# braids_v50.net
KiCad netlist of a schematic drawn in EAGLE
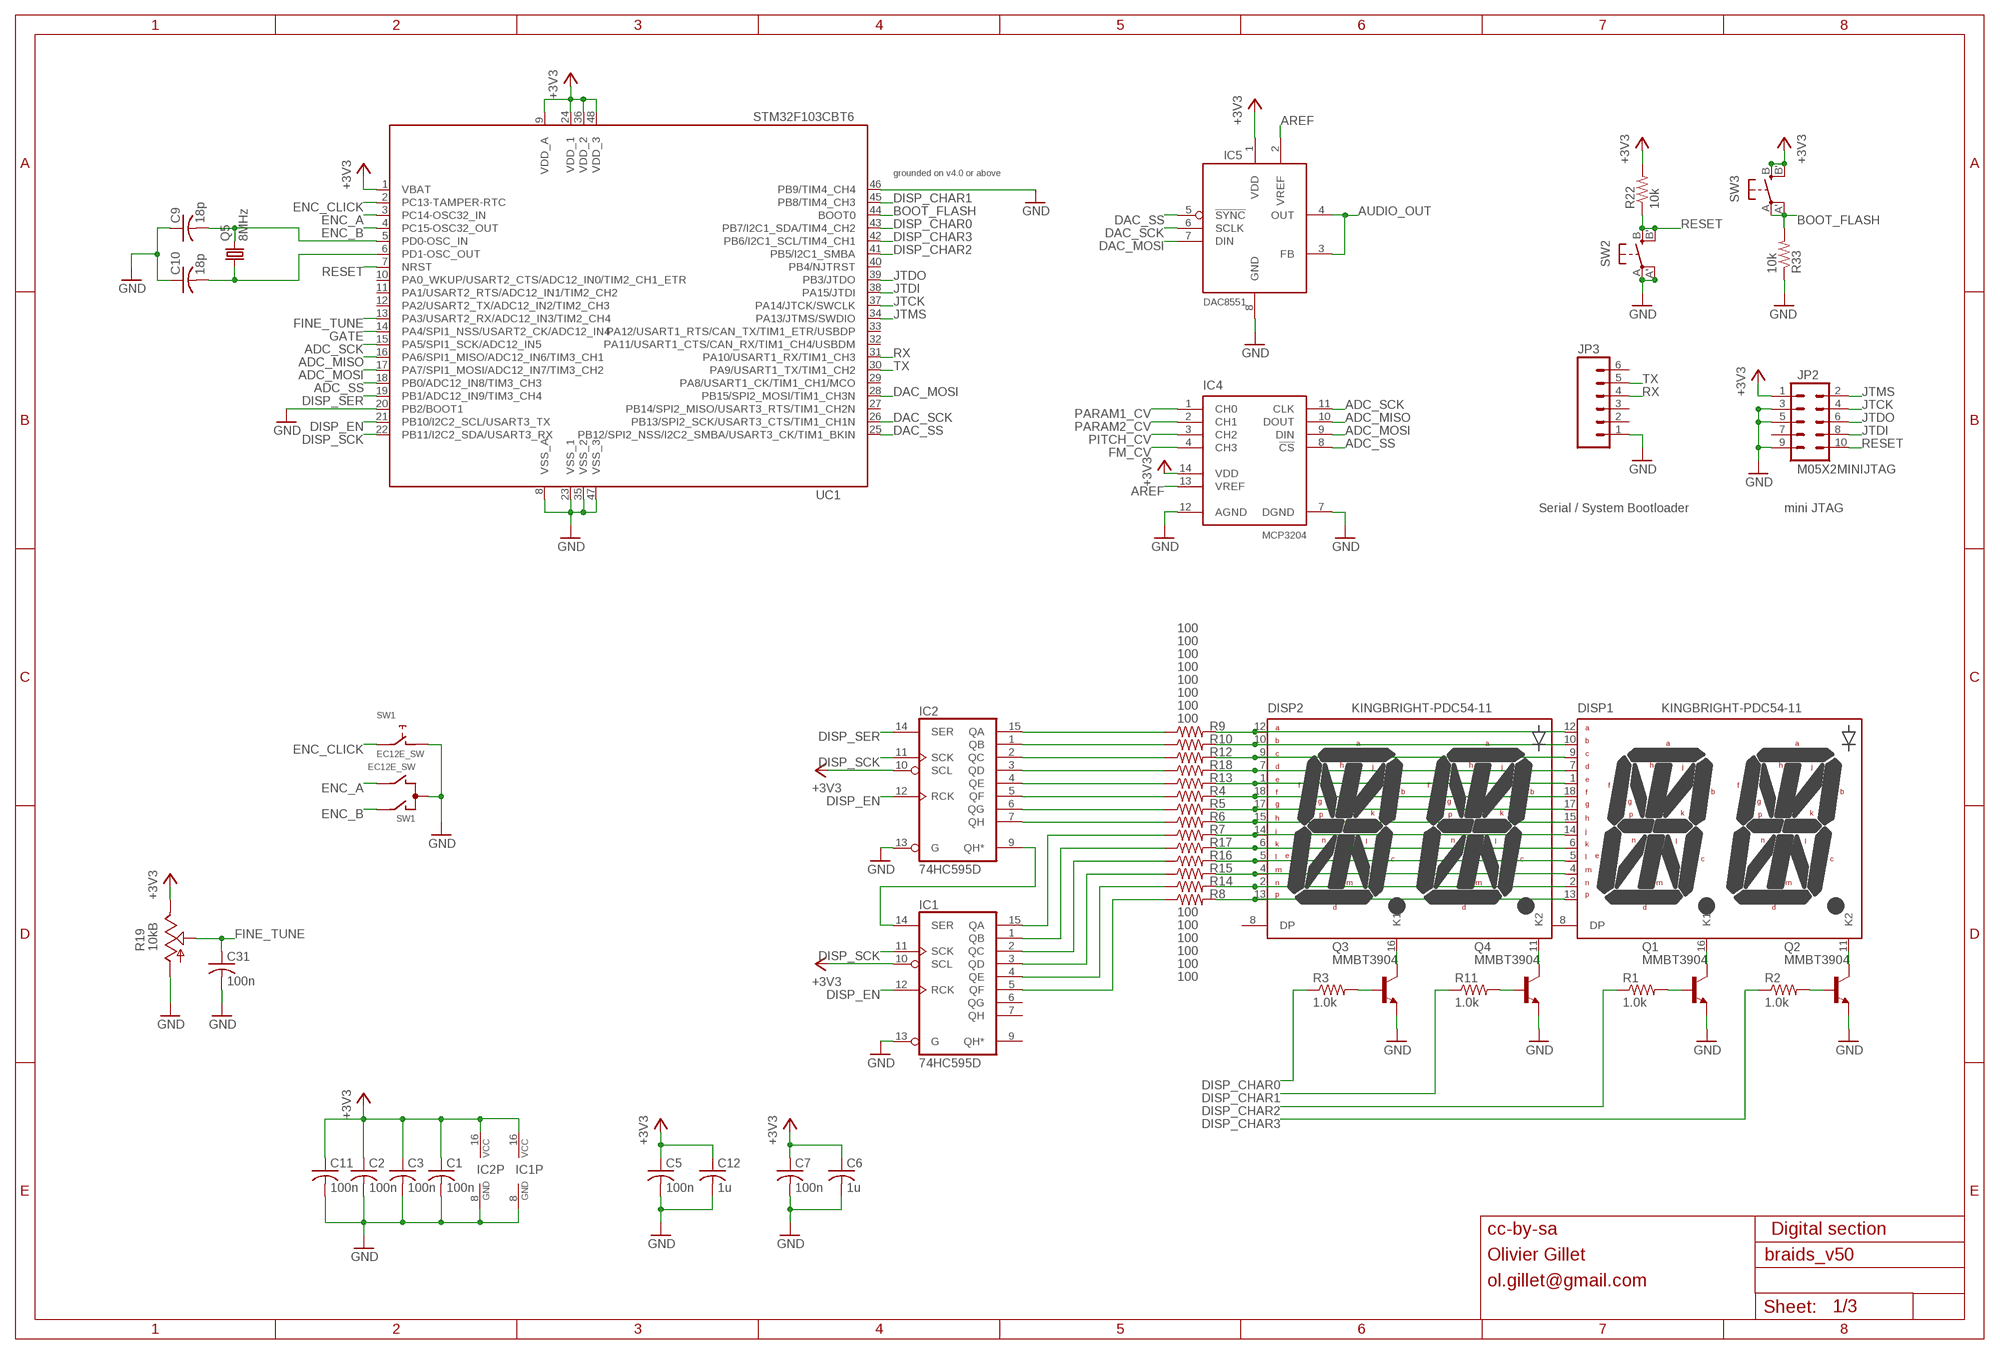
[diagram p0: schematic, sheet 1]
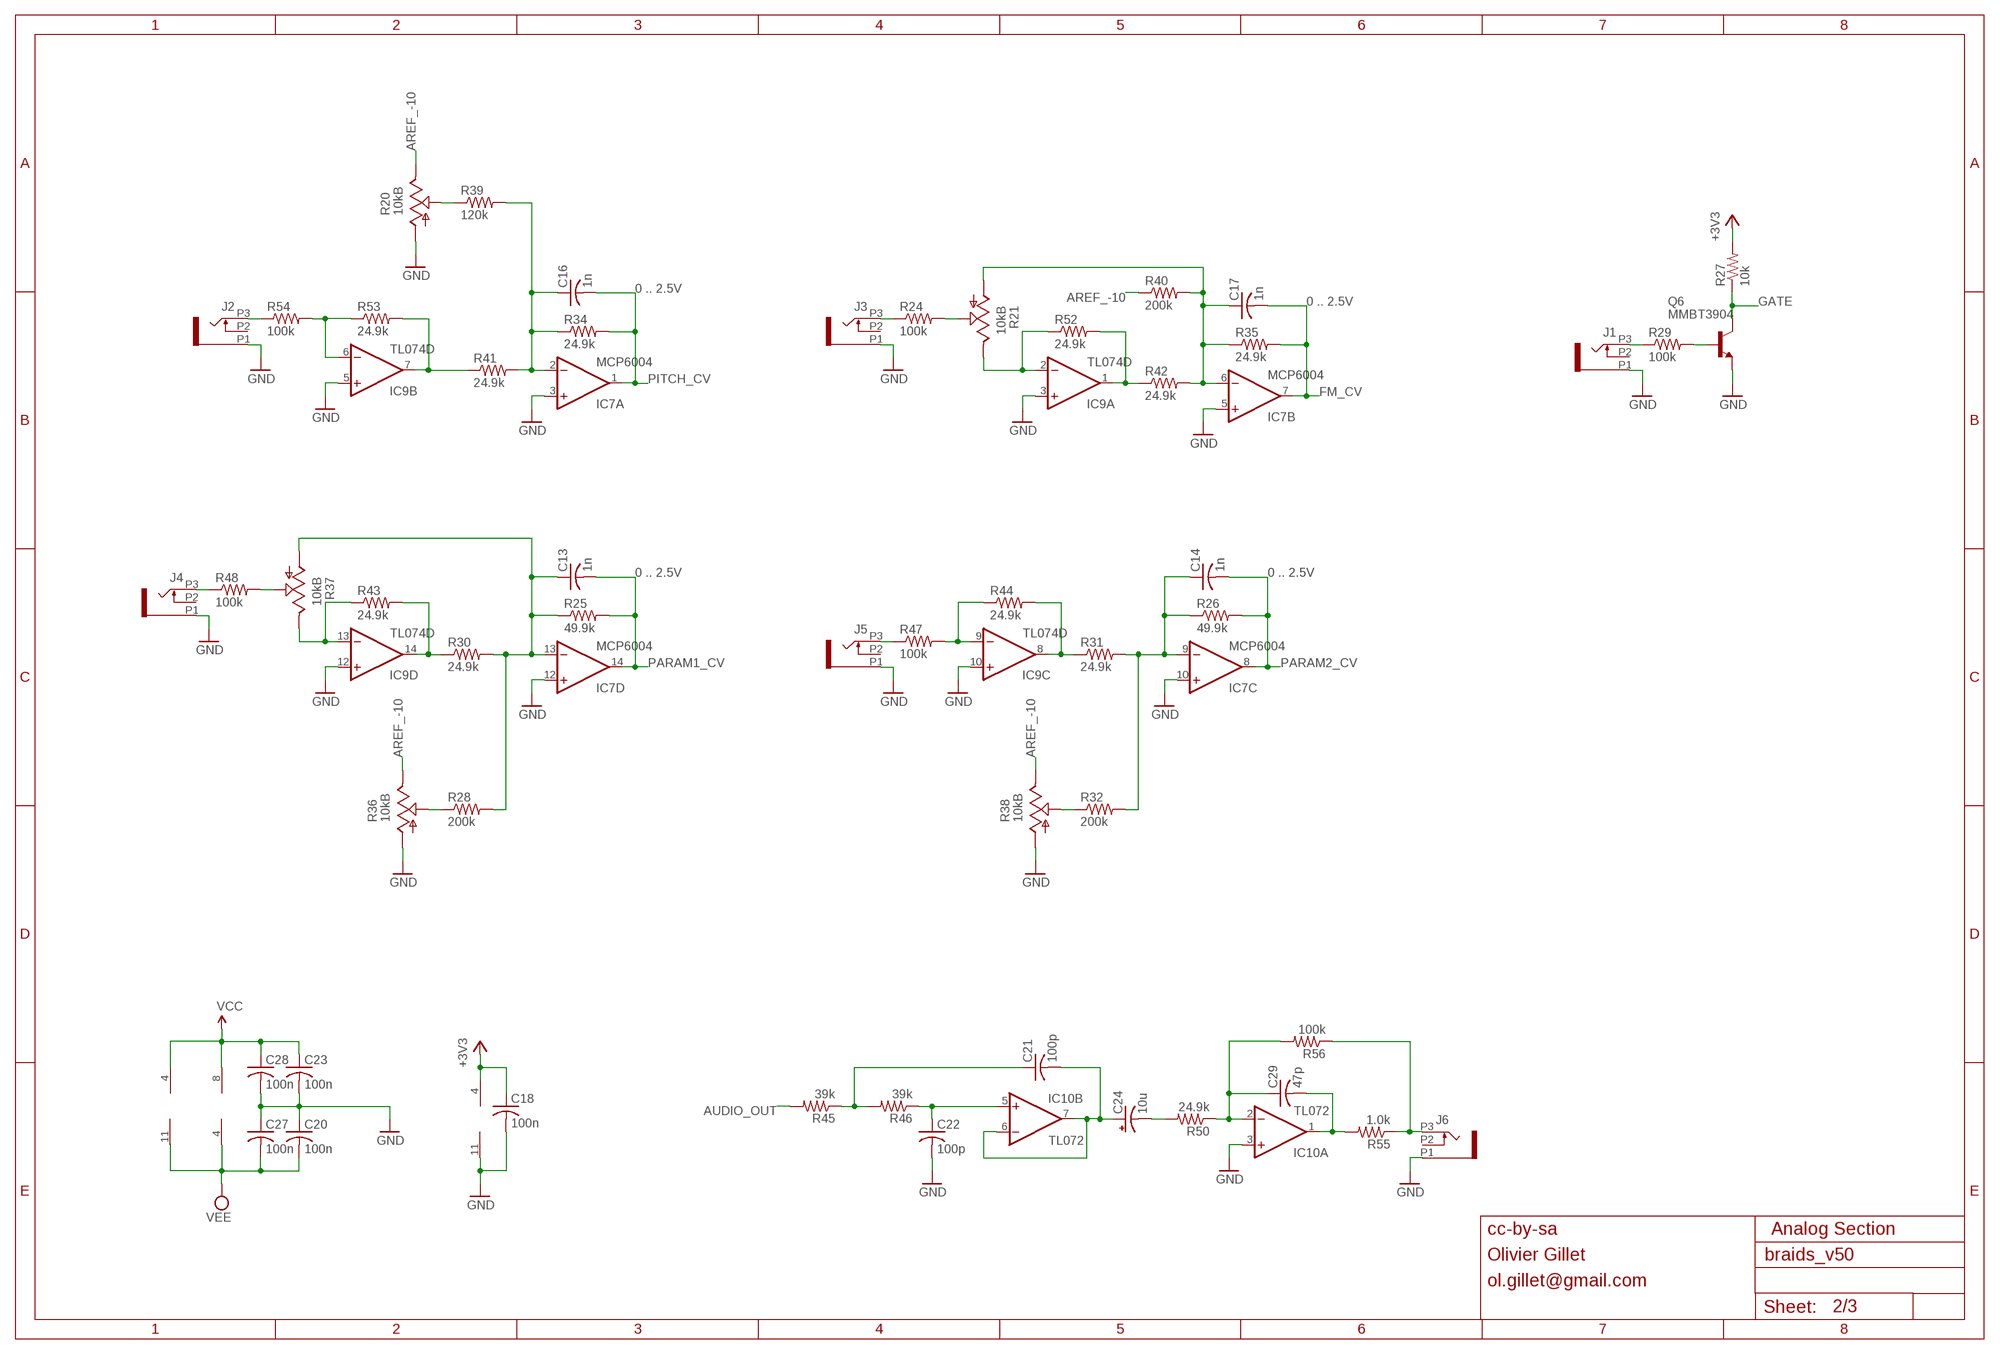
[diagram p1: schematic, sheet 2]
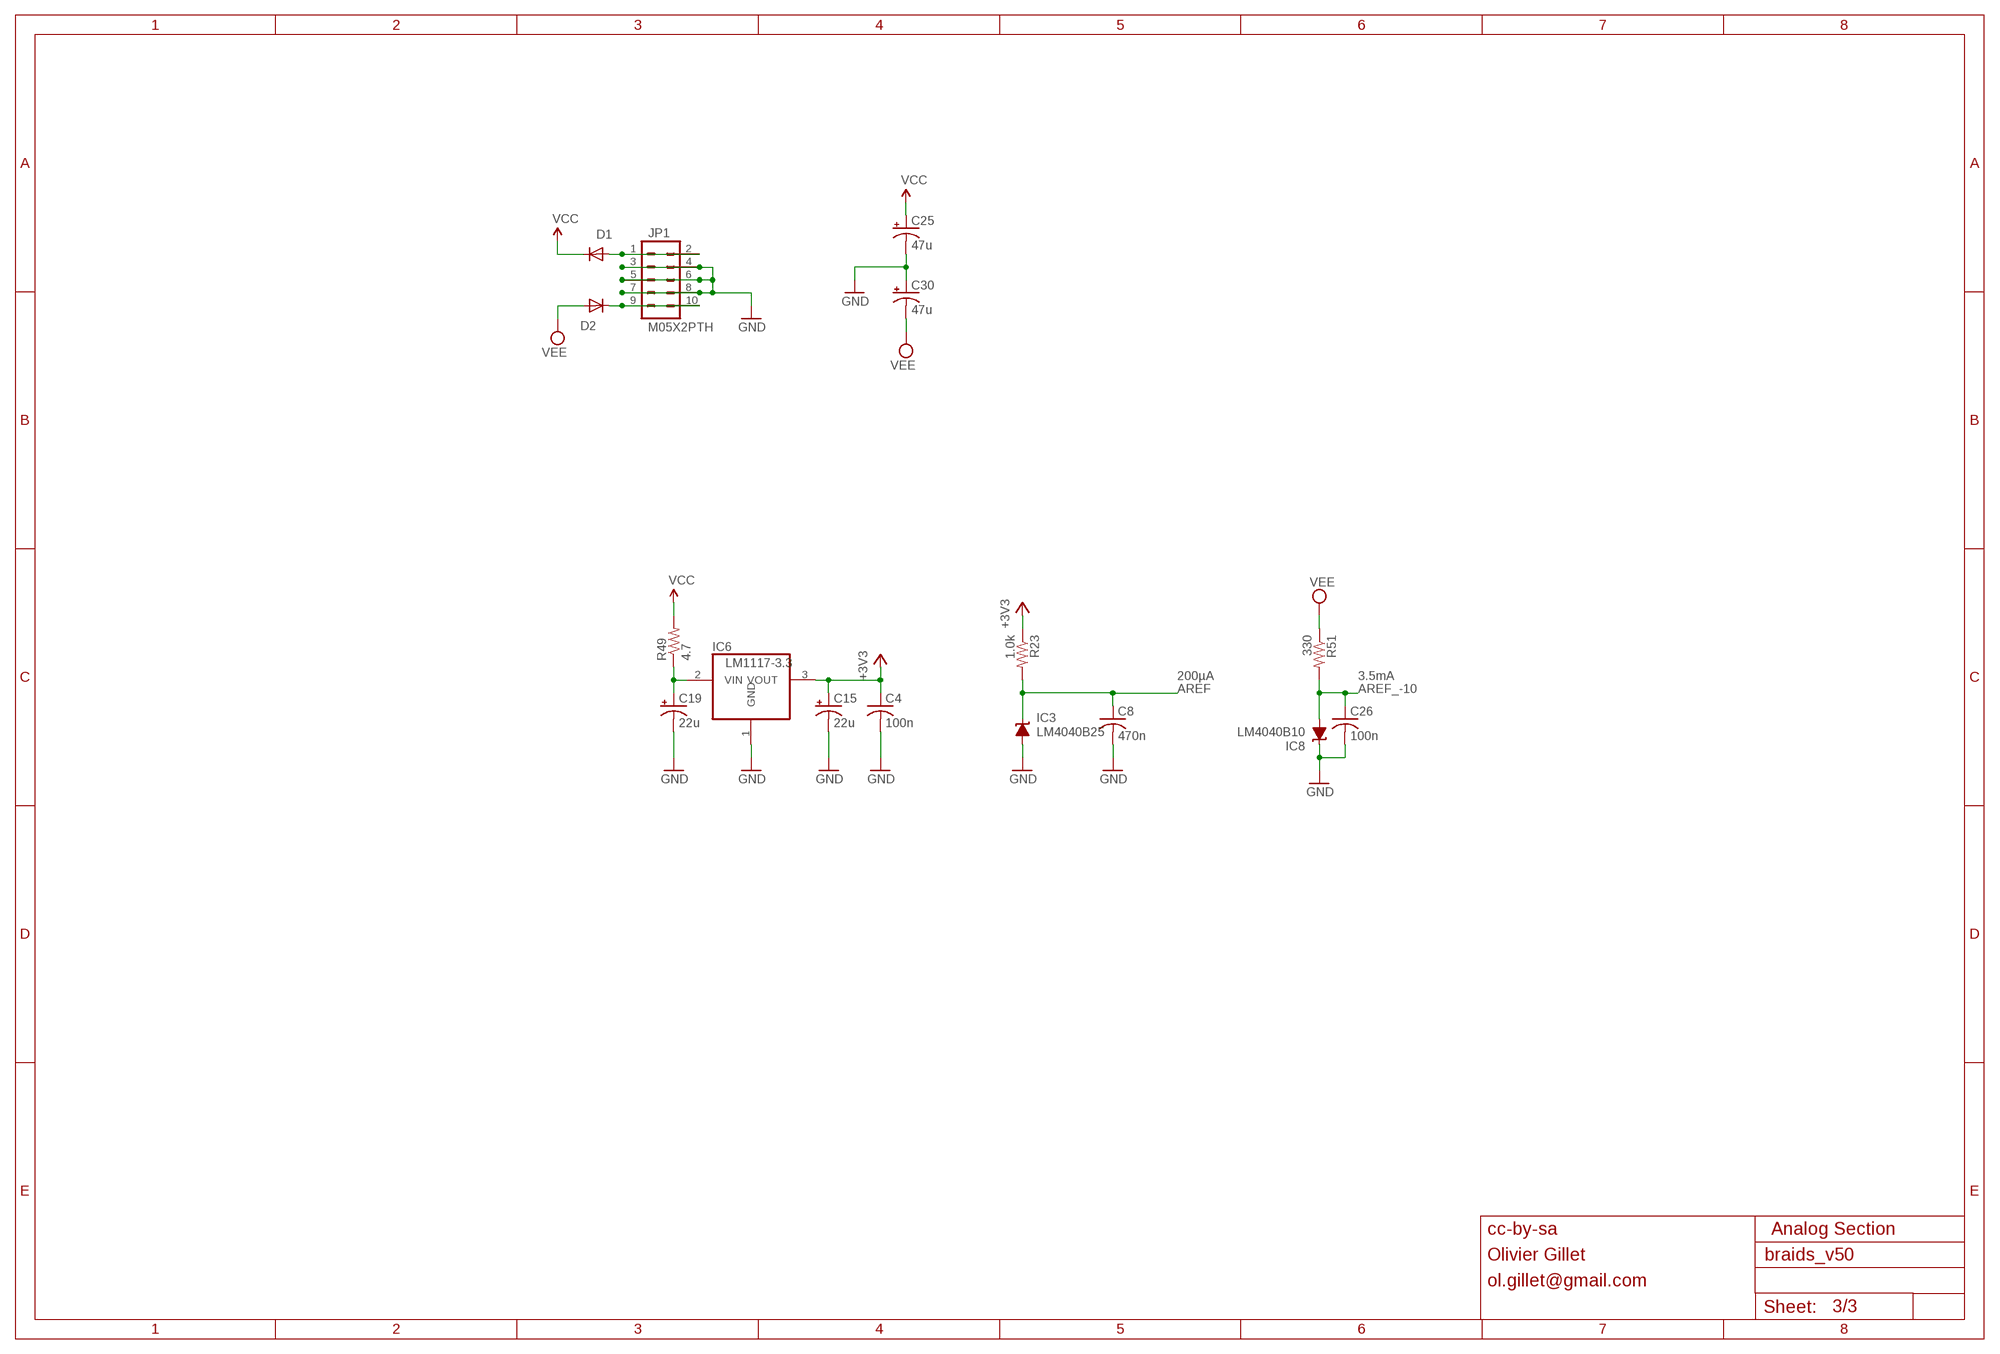
[diagram p2: schematic, sheet 3]

(export (version "E")
  (design (tool "Eeschema 10.0.6"))
  (components
    (comp (ref "C13")
      (value "1n")
      (footprint "eagle-import:C0603")
      (libsource (lib "eagle-import") (part "C-USC0603"))
    )
    (comp (ref "C14")
      (value "1n")
      (footprint "eagle-import:C0603")
      (libsource (lib "eagle-import") (part "C-USC0603"))
    )
    (comp (ref "C16")
      (value "1n")
      (footprint "eagle-import:C0603")
      (libsource (lib "eagle-import") (part "C-USC0603"))
    )
    (comp (ref "C17")
      (value "1n")
      (footprint "eagle-import:C0603")
      (libsource (lib "eagle-import") (part "C-USC0603"))
    )
    (comp (ref "C18")
      (value "100n")
      (footprint "eagle-import:C0603")
      (libsource (lib "eagle-import") (part "C-USC0603"))
    )
    (comp (ref "C20")
      (value "100n")
      (footprint "eagle-import:C0603")
      (libsource (lib "eagle-import") (part "C-USC0603"))
    )
    (comp (ref "C21")
      (value "100p")
      (footprint "eagle-import:C0603")
      (libsource (lib "eagle-import") (part "C-USC0603"))
    )
    (comp (ref "C22")
      (value "100p")
      (footprint "eagle-import:C0603")
      (libsource (lib "eagle-import") (part "C-USC0603"))
    )
    (comp (ref "C23")
      (value "100n")
      (footprint "eagle-import:C0603")
      (libsource (lib "eagle-import") (part "C-USC0603"))
    )
    (comp (ref "C24")
      (value "10u")
      (footprint "eagle-import:PANASONIC_B")
      (libsource (lib "eagle-import") (part "CPOL-USB"))
    )
    (comp (ref "C27")
      (value "100n")
      (footprint "eagle-import:C0603")
      (libsource (lib "eagle-import") (part "C-USC0603"))
    )
    (comp (ref "C28")
      (value "100n")
      (footprint "eagle-import:C0603")
      (libsource (lib "eagle-import") (part "C-USC0603"))
    )
    (comp (ref "C29")
      (value "47p")
      (footprint "eagle-import:C0603")
      (libsource (lib "eagle-import") (part "C-USC0603"))
    )
    (comp (ref "IC7")
      (value "MCP6004")
      (footprint "eagle-import:SO14")
      (libsource (lib "eagle-import") (part "TL074D"))
    )
    (comp (ref "IC9")
      (value "TL074D")
      (footprint "eagle-import:SO14")
      (libsource (lib "eagle-import") (part "TL074D"))
    )
    (comp (ref "IC10")
      (value "TL072")
      (footprint "eagle-import:SO08")
      (libsource (lib "eagle-import") (part "TL072D"))
    )
    (comp (ref "J1")
      (value "PJ301_THONKICONN6")
      (footprint "eagle-import:WQP_PJ_301M6")
      (libsource (lib "eagle-import") (part "PJ301_THONKICONN6"))
    )
    (comp (ref "J2")
      (value "PJ301_THONKICONN6")
      (footprint "eagle-import:WQP_PJ_301M6")
      (libsource (lib "eagle-import") (part "PJ301_THONKICONN6"))
    )
    (comp (ref "J3")
      (value "PJ301_THONKICONN6")
      (footprint "eagle-import:WQP_PJ_301M6")
      (libsource (lib "eagle-import") (part "PJ301_THONKICONN6"))
    )
    (comp (ref "J4")
      (value "PJ301_THONKICONN6")
      (footprint "eagle-import:WQP_PJ_301M6")
      (libsource (lib "eagle-import") (part "PJ301_THONKICONN6"))
    )
    (comp (ref "J5")
      (value "PJ301_THONKICONN6")
      (footprint "eagle-import:WQP_PJ_301M6")
      (libsource (lib "eagle-import") (part "PJ301_THONKICONN6"))
    )
    (comp (ref "J6")
      (value "PJ301_THONKICONN6")
      (footprint "eagle-import:WQP_PJ_301M6")
      (libsource (lib "eagle-import") (part "PJ301_THONKICONN6"))
    )
    (comp (ref "Q6")
      (value "MMBT3904")
      (footprint "eagle-import:SOT23-BEC")
      (libsource (lib "eagle-import") (part "-NPN-SOT23-BECMMBT3904LT1"))
    )
    (comp (ref "R20")
      (value "10kB")
      (footprint "eagle-import:ALPS_POT_VERTICAL_PS")
      (libsource (lib "eagle-import") (part "POT_USVERTICAL_PS"))
    )
    (comp (ref "R21")
      (value "10kB")
      (footprint "eagle-import:ALPS_POT_VERTICAL_PS")
      (libsource (lib "eagle-import") (part "POT_USVERTICAL_PS"))
    )
    (comp (ref "R24")
      (value "100k")
      (footprint "eagle-import:R0603")
      (libsource (lib "eagle-import") (part "R-US_R0603"))
    )
    (comp (ref "R25")
      (value "49.9k")
      (footprint "eagle-import:R0603")
      (libsource (lib "eagle-import") (part "R-US_R0603"))
    )
    (comp (ref "R26")
      (value "49.9k")
      (footprint "eagle-import:R0603")
      (libsource (lib "eagle-import") (part "R-US_R0603"))
    )
    (comp (ref "R27")
      (value "10k")
      (footprint "eagle-import:R0603")
      (libsource (lib "eagle-import") (part "R-US_R0603"))
    )
    (comp (ref "R28")
      (value "200k")
      (footprint "eagle-import:R0603")
      (libsource (lib "eagle-import") (part "R-US_R0603"))
    )
    (comp (ref "R29")
      (value "100k")
      (footprint "eagle-import:R0603")
      (libsource (lib "eagle-import") (part "R-US_R0603"))
    )
    (comp (ref "R30")
      (value "24.9k")
      (footprint "eagle-import:R0603")
      (libsource (lib "eagle-import") (part "R-US_R0603"))
    )
    (comp (ref "R31")
      (value "24.9k")
      (footprint "eagle-import:R0603")
      (libsource (lib "eagle-import") (part "R-US_R0603"))
    )
    (comp (ref "R32")
      (value "200k")
      (footprint "eagle-import:R0603")
      (libsource (lib "eagle-import") (part "R-US_R0603"))
    )
    (comp (ref "R34")
      (value "24.9k")
      (footprint "eagle-import:R0603")
      (libsource (lib "eagle-import") (part "R-US_R0603"))
    )
    (comp (ref "R35")
      (value "24.9k")
      (footprint "eagle-import:R0603")
      (libsource (lib "eagle-import") (part "R-US_R0603"))
    )
    (comp (ref "R36")
      (value "10kB")
      (footprint "eagle-import:ALPS_POT_VERTICAL_PS")
      (libsource (lib "eagle-import") (part "POT_USVERTICAL_PS"))
    )
    (comp (ref "R37")
      (value "10kB")
      (footprint "eagle-import:ALPS_POT_VERTICAL_PS")
      (libsource (lib "eagle-import") (part "POT_USVERTICAL_PS"))
    )
    (comp (ref "R38")
      (value "10kB")
      (footprint "eagle-import:ALPS_POT_VERTICAL_PS")
      (libsource (lib "eagle-import") (part "POT_USVERTICAL_PS"))
    )
    (comp (ref "R39")
      (value "120k")
      (footprint "eagle-import:R0603")
      (libsource (lib "eagle-import") (part "R-US_R0603"))
    )
    (comp (ref "R40")
      (value "200k")
      (footprint "eagle-import:R0603")
      (libsource (lib "eagle-import") (part "R-US_R0603"))
    )
    (comp (ref "R41")
      (value "24.9k")
      (footprint "eagle-import:R0603")
      (libsource (lib "eagle-import") (part "R-US_R0603"))
    )
    (comp (ref "R42")
      (value "24.9k")
      (footprint "eagle-import:R0603")
      (libsource (lib "eagle-import") (part "R-US_R0603"))
    )
    (comp (ref "R43")
      (value "24.9k")
      (footprint "eagle-import:R0603")
      (libsource (lib "eagle-import") (part "R-US_R0603"))
    )
    (comp (ref "R44")
      (value "24.9k")
      (footprint "eagle-import:R0603")
      (libsource (lib "eagle-import") (part "R-US_R0603"))
    )
    (comp (ref "R45")
      (value "39k")
      (footprint "eagle-import:R0603")
      (libsource (lib "eagle-import") (part "R-US_R0603"))
    )
    (comp (ref "R46")
      (value "39k")
      (footprint "eagle-import:R0603")
      (libsource (lib "eagle-import") (part "R-US_R0603"))
    )
    (comp (ref "R47")
      (value "100k")
      (footprint "eagle-import:R0603")
      (libsource (lib "eagle-import") (part "R-US_R0603"))
    )
    (comp (ref "R48")
      (value "100k")
      (footprint "eagle-import:R0603")
      (libsource (lib "eagle-import") (part "R-US_R0603"))
    )
    (comp (ref "R50")
      (value "24.9k")
      (footprint "eagle-import:R0603")
      (libsource (lib "eagle-import") (part "R-US_R0603"))
    )
    (comp (ref "R52")
      (value "24.9k")
      (footprint "eagle-import:R0603")
      (libsource (lib "eagle-import") (part "R-US_R0603"))
    )
    (comp (ref "R53")
      (value "24.9k")
      (footprint "eagle-import:R0603")
      (libsource (lib "eagle-import") (part "R-US_R0603"))
    )
    (comp (ref "R54")
      (value "100k")
      (footprint "eagle-import:R0603")
      (libsource (lib "eagle-import") (part "R-US_R0603"))
    )
    (comp (ref "R55")
      (value "1.0k")
      (footprint "eagle-import:R0603")
      (libsource (lib "eagle-import") (part "R-US_R0603"))
    )
    (comp (ref "R56")
      (value "100k")
      (footprint "eagle-import:R0603")
      (libsource (lib "eagle-import") (part "R-US_R0603"))
    )
    (comp (ref "C1")
      (value "100n")
      (footprint "eagle-import:C0603")
      (libsource (lib "eagle-import") (part "C-USC0603"))
    )
    (comp (ref "C2")
      (value "100n")
      (footprint "eagle-import:C0603")
      (libsource (lib "eagle-import") (part "C-USC0603"))
    )
    (comp (ref "C3")
      (value "100n")
      (footprint "eagle-import:C0603")
      (libsource (lib "eagle-import") (part "C-USC0603"))
    )
    (comp (ref "C5")
      (value "100n")
      (footprint "eagle-import:C0603")
      (libsource (lib "eagle-import") (part "C-USC0603"))
    )
    (comp (ref "C6")
      (value "1u")
      (footprint "eagle-import:C0603")
      (libsource (lib "eagle-import") (part "C-USC0603"))
    )
    (comp (ref "C7")
      (value "100n")
      (footprint "eagle-import:C0603")
      (libsource (lib "eagle-import") (part "C-USC0603"))
    )
    (comp (ref "C9")
      (value "18p")
      (footprint "eagle-import:C0603")
      (libsource (lib "eagle-import") (part "C-USC0603"))
    )
    (comp (ref "C10")
      (value "18p")
      (footprint "eagle-import:C0603")
      (libsource (lib "eagle-import") (part "C-USC0603"))
    )
    (comp (ref "C11")
      (value "100n")
      (footprint "eagle-import:C0603")
      (libsource (lib "eagle-import") (part "C-USC0603"))
    )
    (comp (ref "C12")
      (value "1u")
      (footprint "eagle-import:C0603")
      (libsource (lib "eagle-import") (part "C-USC0603"))
    )
    (comp (ref "C31")
      (value "100n")
      (footprint "eagle-import:C0603")
      (libsource (lib "eagle-import") (part "C-USC0603"))
    )
    (comp (ref "DISP1")
      (value "KINGBRIGHT-PDC54-11")
      (footprint "eagle-import:PDC54")
      (libsource (lib "eagle-import") (part "KINGBRIGHT-PDC54-11"))
    )
    (comp (ref "DISP2")
      (value "KINGBRIGHT-PDC54-11")
      (footprint "eagle-import:PDC54")
      (libsource (lib "eagle-import") (part "KINGBRIGHT-PDC54-11"))
    )
    (comp (ref "IC1")
      (value "74HC595D")
      (footprint "eagle-import:SO16")
      (libsource (lib "eagle-import") (part "74595DHC"))
    )
    (comp (ref "IC2")
      (value "74HC595D")
      (footprint "eagle-import:SO16")
      (libsource (lib "eagle-import") (part "74595DHC"))
    )
    (comp (ref "IC4")
      (value "MCP3204")
      (footprint "eagle-import:SO14")
      (libsource (lib "eagle-import") (part "MCP3302"))
    )
    (comp (ref "IC5")
      (value "DAC8551")
      (footprint "eagle-import:MSOP-8")
      (libsource (lib "eagle-import") (part "DAC855X"))
    )
    (comp (ref "JP2")
      (value "M05X2MINIJTAG")
      (footprint "eagle-import:2X5-1.27")
      (libsource (lib "eagle-import") (part "M05X2MINIJTAG"))
    )
    (comp (ref "JP3")
      (value "M06SIP")
      (footprint "eagle-import:1X06")
      (libsource (lib "eagle-import") (part "M06SIP"))
    )
    (comp (ref "Q1")
      (value "MMBT3904")
      (footprint "eagle-import:SOT23-BEC")
      (libsource (lib "eagle-import") (part "-NPN-SOT23-BECMMBT3904LT1"))
    )
    (comp (ref "Q2")
      (value "MMBT3904")
      (footprint "eagle-import:SOT23-BEC")
      (libsource (lib "eagle-import") (part "-NPN-SOT23-BECMMBT3904LT1"))
    )
    (comp (ref "Q3")
      (value "MMBT3904")
      (footprint "eagle-import:SOT23-BEC")
      (libsource (lib "eagle-import") (part "-NPN-SOT23-BECMMBT3904LT1"))
    )
    (comp (ref "Q4")
      (value "MMBT3904")
      (footprint "eagle-import:SOT23-BEC")
      (libsource (lib "eagle-import") (part "-NPN-SOT23-BECMMBT3904LT1"))
    )
    (comp (ref "Q5")
      (value "8MHz")
      (footprint "eagle-import:HC49UP")
      (libsource (lib "eagle-import") (part "CRYSTALHC49UP"))
    )
    (comp (ref "R1")
      (value "1.0k")
      (footprint "eagle-import:R0603")
      (libsource (lib "eagle-import") (part "R-US_R0603"))
    )
    (comp (ref "R2")
      (value "1.0k")
      (footprint "eagle-import:R0603")
      (libsource (lib "eagle-import") (part "R-US_R0603"))
    )
    (comp (ref "R3")
      (value "1.0k")
      (footprint "eagle-import:R0603")
      (libsource (lib "eagle-import") (part "R-US_R0603"))
    )
    (comp (ref "R4")
      (value "100")
      (footprint "eagle-import:R0603")
      (libsource (lib "eagle-import") (part "R-US_R0603"))
    )
    (comp (ref "R5")
      (value "100")
      (footprint "eagle-import:R0603")
      (libsource (lib "eagle-import") (part "R-US_R0603"))
    )
    (comp (ref "R6")
      (value "100")
      (footprint "eagle-import:R0603")
      (libsource (lib "eagle-import") (part "R-US_R0603"))
    )
    (comp (ref "R7")
      (value "100")
      (footprint "eagle-import:R0603")
      (libsource (lib "eagle-import") (part "R-US_R0603"))
    )
    (comp (ref "R8")
      (value "100")
      (footprint "eagle-import:R0603")
      (libsource (lib "eagle-import") (part "R-US_R0603"))
    )
    (comp (ref "R9")
      (value "100")
      (footprint "eagle-import:R0603")
      (libsource (lib "eagle-import") (part "R-US_R0603"))
    )
    (comp (ref "R10")
      (value "100")
      (footprint "eagle-import:R0603")
      (libsource (lib "eagle-import") (part "R-US_R0603"))
    )
    (comp (ref "R11")
      (value "1.0k")
      (footprint "eagle-import:R0603")
      (libsource (lib "eagle-import") (part "R-US_R0603"))
    )
    (comp (ref "R12")
      (value "100")
      (footprint "eagle-import:R0603")
      (libsource (lib "eagle-import") (part "R-US_R0603"))
    )
    (comp (ref "R13")
      (value "100")
      (footprint "eagle-import:R0603")
      (libsource (lib "eagle-import") (part "R-US_R0603"))
    )
    (comp (ref "R14")
      (value "100")
      (footprint "eagle-import:R0603")
      (libsource (lib "eagle-import") (part "R-US_R0603"))
    )
    (comp (ref "R15")
      (value "100")
      (footprint "eagle-import:R0603")
      (libsource (lib "eagle-import") (part "R-US_R0603"))
    )
    (comp (ref "R16")
      (value "100")
      (footprint "eagle-import:R0603")
      (libsource (lib "eagle-import") (part "R-US_R0603"))
    )
    (comp (ref "R17")
      (value "100")
      (footprint "eagle-import:R0603")
      (libsource (lib "eagle-import") (part "R-US_R0603"))
    )
    (comp (ref "R18")
      (value "100")
      (footprint "eagle-import:R0603")
      (libsource (lib "eagle-import") (part "R-US_R0603"))
    )
    (comp (ref "R19")
      (value "10kB")
      (footprint "eagle-import:ALPS_POT_VERTICAL_PS")
      (libsource (lib "eagle-import") (part "POT_USVERTICAL_PS"))
    )
    (comp (ref "R22")
      (value "10k")
      (footprint "eagle-import:R0603")
      (libsource (lib "eagle-import") (part "R-US_R0603"))
    )
    (comp (ref "R33")
      (value "10k")
      (footprint "eagle-import:R0603")
      (libsource (lib "eagle-import") (part "R-US_R0603"))
    )
    (comp (ref "SW1")
      (value "EC12E_SW")
      (footprint "eagle-import:ALPS_EC12E_SW")
      (libsource (lib "eagle-import") (part "EC12E_SW"))
    )
    (comp (ref "SW2")
      (value "EVQQ2")
      (footprint "eagle-import:EVQ-Q2")
      (libsource (lib "eagle-import") (part "EVQQ2"))
    )
    (comp (ref "SW3")
      (value "EVQQ2")
      (footprint "eagle-import:EVQ-Q2")
      (libsource (lib "eagle-import") (part "EVQQ2"))
    )
    (comp (ref "UC1")
      (value "STM32F103CBT6")
      (footprint "eagle-import:LQFP48")
      (libsource (lib "eagle-import") (part "STM32F103CB"))
    )
    (comp (ref "C4")
      (value "100n")
      (footprint "eagle-import:C0603")
      (libsource (lib "eagle-import") (part "C-USC0603"))
    )
    (comp (ref "C8")
      (value "470n")
      (footprint "eagle-import:C0603")
      (libsource (lib "eagle-import") (part "C-USC0603"))
    )
    (comp (ref "C15")
      (value "22u")
      (footprint "eagle-import:PANASONIC_C")
      (libsource (lib "eagle-import") (part "CPOL-USC"))
    )
    (comp (ref "C19")
      (value "22u")
      (footprint "eagle-import:PANASONIC_C")
      (libsource (lib "eagle-import") (part "CPOL-USC"))
    )
    (comp (ref "C25")
      (value "47u")
      (footprint "eagle-import:PANASONIC_D")
      (libsource (lib "eagle-import") (part "CPOL-USD"))
    )
    (comp (ref "C26")
      (value "100n")
      (footprint "eagle-import:C0603")
      (libsource (lib "eagle-import") (part "C-USC0603"))
    )
    (comp (ref "C30")
      (value "47u")
      (footprint "eagle-import:PANASONIC_D")
      (libsource (lib "eagle-import") (part "CPOL-USD"))
    )
    (comp (ref "D1")
      (value "1N5819HW")
      (footprint "eagle-import:SOD123")
      (libsource (lib "eagle-import") (part "DIODE-SOD123"))
    )
    (comp (ref "D2")
      (value "1N5819HW")
      (footprint "eagle-import:SOD123")
      (libsource (lib "eagle-import") (part "DIODE-SOD123"))
    )
    (comp (ref "IC3")
      (value "LM4040B25")
      (footprint "eagle-import:DBZ_R-PDSO-G3")
      (libsource (lib "eagle-import") (part "LM4041DBZB12"))
    )
    (comp (ref "IC6")
      (value "LM1117-3.3")
      (footprint "eagle-import:TO252")
      (libsource (lib "eagle-import") (part "REG1117T"))
    )
    (comp (ref "IC8")
      (value "LM4040B10")
      (footprint "eagle-import:DBZ_R-PDSO-G3")
      (libsource (lib "eagle-import") (part "LM4041DBZB12"))
    )
    (comp (ref "JP1")
      (value "M05X2PTH")
      (footprint "eagle-import:AVR_ICSP")
      (libsource (lib "eagle-import") (part "M05X2PTH"))
    )
    (comp (ref "R23")
      (value "1.0k")
      (footprint "eagle-import:R0603")
      (libsource (lib "eagle-import") (part "R-US_R0603"))
    )
    (comp (ref "R49")
      (value "4.7")
      (footprint "eagle-import:R1206")
      (libsource (lib "eagle-import") (part "R-US_R1206"))
    )
    (comp (ref "R51")
      (value "330")
      (footprint "eagle-import:R0603")
      (libsource (lib "eagle-import") (part "R-US_R0603"))
    )
  )
  (nets
    (net (code "1") (name "+3V3") (class "Default")
      (node (ref "C1") (pin "1") (pinfunction "1_1") (pintype "passive"))
      (node (ref "C11") (pin "1") (pinfunction "1_1") (pintype "passive"))
      (node (ref "C12") (pin "1") (pinfunction "1_1") (pintype "passive"))
      (node (ref "C15") (pin "+") (pinfunction "+_+") (pintype "passive"))
      (node (ref "C18") (pin "1") (pinfunction "1_1") (pintype "passive"))
      (node (ref "C2") (pin "1") (pinfunction "1_1") (pintype "passive"))
      (node (ref "C3") (pin "1") (pinfunction "1_1") (pintype "passive"))
      (node (ref "C4") (pin "1") (pinfunction "1_1") (pintype "passive"))
      (node (ref "C5") (pin "1") (pinfunction "1_1") (pintype "passive"))
      (node (ref "C6") (pin "1") (pinfunction "1_1") (pintype "passive"))
      (node (ref "C7") (pin "1") (pinfunction "1_1") (pintype "passive"))
      (node (ref "IC1") (pin "10") (pinfunction "SCL_10") (pintype "input"))
      (node (ref "IC1") (pin "16") (pinfunction "VCC_16") (pintype "power_in"))
      (node (ref "IC2") (pin "10") (pinfunction "SCL_10") (pintype "input"))
      (node (ref "IC2") (pin "16") (pinfunction "VCC_16") (pintype "power_in"))
      (node (ref "IC4") (pin "14") (pinfunction "VDD_14") (pintype "bidirectional"))
      (node (ref "IC5") (pin "1") (pinfunction "VDD_1") (pintype "power_in"))
      (node (ref "IC6") (pin "3") (pinfunction "VOUT_3") (pintype "output"))
      (node (ref "IC7") (pin "4") (pinfunction "V+_4") (pintype "power_in"))
      (node (ref "JP2") (pin "1") (pinfunction "1_1") (pintype "passive"))
      (node (ref "R19") (pin "P$1") (pinfunction "E_P$1") (pintype "passive"))
      (node (ref "R22") (pin "2") (pinfunction "2_2") (pintype "passive"))
      (node (ref "R23") (pin "1") (pinfunction "1_1") (pintype "passive"))
      (node (ref "R27") (pin "2") (pinfunction "2_2") (pintype "passive"))
      (node (ref "SW3") (pin "B") (pinfunction "S_B") (pintype "passive"))
      (node (ref "SW3") (pin "B'") (pinfunction "S1_B'") (pintype "passive"))
      (node (ref "UC1") (pin "1") (pinfunction "VBAT_1") (pintype "power_in"))
      (node (ref "UC1") (pin "24") (pinfunction "VDD_1_24") (pintype "power_in"))
      (node (ref "UC1") (pin "36") (pinfunction "VDD_2_36") (pintype "power_in"))
      (node (ref "UC1") (pin "48") (pinfunction "VDD_3_48") (pintype "power_in"))
      (node (ref "UC1") (pin "9") (pinfunction "VDD_A_9") (pintype "power_in"))
    )
    (net (code "2") (name "ADC_MISO") (class "Default")
      (node (ref "IC4") (pin "10") (pinfunction "DOUT_10") (pintype "bidirectional"))
      (node (ref "UC1") (pin "16") (pinfunction "PA6/SPI1_MISO/ADC12_IN6/TIM3_CH1_16") (pintype "bidirectional"))
    )
    (net (code "3") (name "ADC_MOSI") (class "Default")
      (node (ref "IC4") (pin "9") (pinfunction "DIN_9") (pintype "bidirectional"))
      (node (ref "UC1") (pin "17") (pinfunction "PA7/SPI1_MOSI/ADC12_IN7/TIM3_CH2_17") (pintype "bidirectional"))
    )
    (net (code "4") (name "ADC_SCK") (class "Default")
      (node (ref "IC4") (pin "11") (pinfunction "CLK_11") (pintype "bidirectional"))
      (node (ref "UC1") (pin "15") (pinfunction "PA5/SPI1_SCK/ADC12_IN5_15") (pintype "bidirectional"))
    )
    (net (code "5") (name "ADC_SS") (class "Default")
      (node (ref "IC4") (pin "8") (pinfunction "~{CS}_8") (pintype "bidirectional"))
      (node (ref "UC1") (pin "18") (pinfunction "PB0/ADC12_IN8/TIM3_CH3_18") (pintype "bidirectional"))
    )
    (net (code "6") (name "AREF") (class "Default")
      (node (ref "C8") (pin "1") (pinfunction "1_1") (pintype "passive"))
      (node (ref "IC3") (pin "1") (pinfunction "C_1") (pintype "passive"))
      (node (ref "IC4") (pin "13") (pinfunction "VREF_13") (pintype "bidirectional"))
      (node (ref "IC5") (pin "2") (pinfunction "VREF_2") (pintype "power_in"))
      (node (ref "R23") (pin "2") (pinfunction "2_2") (pintype "passive"))
    )
    (net (code "7") (name "AREF_-10") (class "Default")
      (node (ref "C26") (pin "1") (pinfunction "1_1") (pintype "passive"))
      (node (ref "IC8") (pin "2") (pinfunction "A_2") (pintype "passive"))
      (node (ref "R20") (pin "P$1") (pinfunction "E_P$1") (pintype "passive"))
      (node (ref "R36") (pin "P$1") (pinfunction "E_P$1") (pintype "passive"))
      (node (ref "R38") (pin "P$1") (pinfunction "E_P$1") (pintype "passive"))
      (node (ref "R40") (pin "1") (pinfunction "1_1") (pintype "passive"))
      (node (ref "R51") (pin "2") (pinfunction "2_2") (pintype "passive"))
    )
    (net (code "8") (name "AUDIO_OUT") (class "Default")
      (node (ref "IC5") (pin "3") (pinfunction "FB_3") (pintype "input"))
      (node (ref "IC5") (pin "4") (pinfunction "OUT_4") (pintype "output"))
      (node (ref "R45") (pin "2") (pinfunction "2_2") (pintype "passive"))
    )
    (net (code "9") (name "BOOT_FLASH") (class "Default")
      (node (ref "R33") (pin "2") (pinfunction "2_2") (pintype "passive"))
      (node (ref "SW3") (pin "A") (pinfunction "P_A") (pintype "passive"))
      (node (ref "SW3") (pin "A'") (pinfunction "P1_A'") (pintype "passive"))
      (node (ref "UC1") (pin "44") (pinfunction "BOOT0_44") (pintype "input"))
    )
    (net (code "10") (name "DAC_MOSI") (class "Default")
      (node (ref "IC5") (pin "7") (pinfunction "DIN_7") (pintype "bidirectional"))
      (node (ref "UC1") (pin "28") (pinfunction "PB15/SPI2_MOSI/TIM1_CH3N_28") (pintype "input"))
    )
    (net (code "11") (name "DAC_SCK") (class "Default")
      (node (ref "IC5") (pin "6") (pinfunction "SCLK_6") (pintype "bidirectional"))
      (node (ref "UC1") (pin "26") (pinfunction "PB13/SPI2_SCK/USART3_CTS/TIM1_CH1N_26") (pintype "input"))
    )
    (net (code "12") (name "DAC_SS") (class "Default")
      (node (ref "IC5") (pin "5") (pinfunction "~{SYNC}_5") (pintype "bidirectional"))
      (node (ref "UC1") (pin "25") (pinfunction "PB12/SPI2_NSS/I2C2_SMBA/USART3_CK/TIM1_BKIN_25") (pintype "input"))
    )
    (net (code "13") (name "DISP_CHAR0") (class "Default")
      (node (ref "R3") (pin "1") (pinfunction "1_1") (pintype "passive"))
      (node (ref "UC1") (pin "43") (pinfunction "PB7/I2C1_SDA/TIM4_CH2_43") (pintype "bidirectional"))
    )
    (net (code "14") (name "DISP_CHAR1") (class "Default")
      (node (ref "R11") (pin "1") (pinfunction "1_1") (pintype "passive"))
      (node (ref "UC1") (pin "45") (pinfunction "PB8/TIM4_CH3_45") (pintype "bidirectional"))
    )
    (net (code "15") (name "DISP_CHAR2") (class "Default")
      (node (ref "R1") (pin "1") (pinfunction "1_1") (pintype "passive"))
      (node (ref "UC1") (pin "41") (pinfunction "PB5/I2C1_SMBA_41") (pintype "input"))
    )
    (net (code "16") (name "DISP_CHAR3") (class "Default")
      (node (ref "R2") (pin "1") (pinfunction "1_1") (pintype "passive"))
      (node (ref "UC1") (pin "42") (pinfunction "PB6/I2C1_SCL/TIM4_CH1_42") (pintype "input"))
    )
    (net (code "17") (name "DISP_EN") (class "Default")
      (node (ref "IC1") (pin "12") (pinfunction "RCK_12") (pintype "input"))
      (node (ref "IC2") (pin "12") (pinfunction "RCK_12") (pintype "input"))
      (node (ref "UC1") (pin "21") (pinfunction "PB10/I2C2_SCL/USART3_TX_21") (pintype "input"))
    )
    (net (code "18") (name "DISP_SCK") (class "Default")
      (node (ref "IC1") (pin "11") (pinfunction "SCK_11") (pintype "input"))
      (node (ref "IC2") (pin "11") (pinfunction "SCK_11") (pintype "input"))
      (node (ref "UC1") (pin "22") (pinfunction "PB11/I2C2_SDA/USART3_RX_22") (pintype "input"))
    )
    (net (code "19") (name "DISP_SER") (class "Default")
      (node (ref "IC2") (pin "14") (pinfunction "SER_14") (pintype "input"))
      (node (ref "UC1") (pin "19") (pinfunction "PB1/ADC12_IN9/TIM3_CH4_19") (pintype "bidirectional"))
    )
    (net (code "20") (name "ENC_A") (class "Default")
      (node (ref "SW1") (pin "B") (pinfunction "B_B") (pintype "passive"))
      (node (ref "UC1") (pin "3") (pinfunction "PC14-OSC32_IN_3") (pintype "input"))
    )
    (net (code "21") (name "ENC_B") (class "Default")
      (node (ref "SW1") (pin "A") (pinfunction "A_A") (pintype "passive"))
      (node (ref "UC1") (pin "4") (pinfunction "PC15-OSC32_OUT_4") (pintype "input"))
    )
    (net (code "22") (name "ENC_CLICK") (class "Default")
      (node (ref "SW1") (pin "E") (pinfunction "2_E") (pintype "passive"))
      (node (ref "UC1") (pin "2") (pinfunction "PC13-TAMPER-RTC_2") (pintype "input"))
    )
    (net (code "23") (name "FINE_TUNE") (class "Default")
      (node (ref "C31") (pin "1") (pinfunction "1_1") (pintype "passive"))
      (node (ref "R19") (pin "P$2") (pinfunction "S_P$2") (pintype "passive"))
      (node (ref "UC1") (pin "13") (pinfunction "PA3/USART2_RX/ADC12_IN3/TIM2_CH4_13") (pintype "bidirectional"))
    )
    (net (code "24") (name "FM_CV") (class "Default")
      (node (ref "C17") (pin "2") (pinfunction "2_2") (pintype "passive"))
      (node (ref "IC4") (pin "4") (pinfunction "CH3_4") (pintype "bidirectional"))
      (node (ref "IC7") (pin "7") (pinfunction "OUT_7") (pintype "output"))
      (node (ref "R35") (pin "2") (pinfunction "2_2") (pintype "passive"))
    )
    (net (code "25") (name "GATE") (class "Default")
      (node (ref "Q6") (pin "C") (pinfunction "C_C") (pintype "passive"))
      (node (ref "R27") (pin "1") (pinfunction "1_1") (pintype "passive"))
      (node (ref "UC1") (pin "14") (pinfunction "PA4/SPI1_NSS/USART2_CK/ADC12_IN4_14") (pintype "bidirectional"))
    )
    (net (code "26") (name "GND") (class "Default")
      (node (ref "C1") (pin "2") (pinfunction "2_2") (pintype "passive"))
      (node (ref "C10") (pin "1") (pinfunction "1_1") (pintype "passive"))
      (node (ref "C11") (pin "2") (pinfunction "2_2") (pintype "passive"))
      (node (ref "C12") (pin "2") (pinfunction "2_2") (pintype "passive"))
      (node (ref "C15") (pin "-") (pinfunction "-_-") (pintype "passive"))
      (node (ref "C18") (pin "2") (pinfunction "2_2") (pintype "passive"))
      (node (ref "C19") (pin "-") (pinfunction "-_-") (pintype "passive"))
      (node (ref "C2") (pin "2") (pinfunction "2_2") (pintype "passive"))
      (node (ref "C20") (pin "1") (pinfunction "1_1") (pintype "passive"))
      (node (ref "C22") (pin "2") (pinfunction "2_2") (pintype "passive"))
      (node (ref "C23") (pin "2") (pinfunction "2_2") (pintype "passive"))
      (node (ref "C25") (pin "-") (pinfunction "-_-") (pintype "passive"))
      (node (ref "C26") (pin "2") (pinfunction "2_2") (pintype "passive"))
      (node (ref "C27") (pin "1") (pinfunction "1_1") (pintype "passive"))
      (node (ref "C28") (pin "2") (pinfunction "2_2") (pintype "passive"))
      (node (ref "C3") (pin "2") (pinfunction "2_2") (pintype "passive"))
      (node (ref "C30") (pin "+") (pinfunction "+_+") (pintype "passive"))
      (node (ref "C31") (pin "2") (pinfunction "2_2") (pintype "passive"))
      (node (ref "C4") (pin "2") (pinfunction "2_2") (pintype "passive"))
      (node (ref "C5") (pin "2") (pinfunction "2_2") (pintype "passive"))
      (node (ref "C6") (pin "2") (pinfunction "2_2") (pintype "passive"))
      (node (ref "C7") (pin "2") (pinfunction "2_2") (pintype "passive"))
      (node (ref "C8") (pin "2") (pinfunction "2_2") (pintype "passive"))
      (node (ref "C9") (pin "1") (pinfunction "1_1") (pintype "passive"))
      (node (ref "IC1") (pin "13") (pinfunction "G_13") (pintype "input"))
      (node (ref "IC1") (pin "8") (pinfunction "GND_8") (pintype "power_in"))
      (node (ref "IC10") (pin "3") (pinfunction "+IN_3") (pintype "input"))
      (node (ref "IC2") (pin "13") (pinfunction "G_13") (pintype "input"))
      (node (ref "IC2") (pin "8") (pinfunction "GND_8") (pintype "power_in"))
      (node (ref "IC3") (pin "2") (pinfunction "A_2") (pintype "passive"))
      (node (ref "IC4") (pin "12") (pinfunction "AGND_12") (pintype "bidirectional"))
      (node (ref "IC4") (pin "7") (pinfunction "DGND_7") (pintype "bidirectional"))
      (node (ref "IC5") (pin "8") (pinfunction "GND_8") (pintype "power_in"))
      (node (ref "IC6") (pin "1") (pinfunction "GND_1") (pintype "power_in"))
      (node (ref "IC7") (pin "10") (pinfunction "+IN_10") (pintype "input"))
      (node (ref "IC7") (pin "11") (pinfunction "V-_11") (pintype "power_in"))
      (node (ref "IC7") (pin "12") (pinfunction "+IN_12") (pintype "input"))
      (node (ref "IC7") (pin "3") (pinfunction "+IN_3") (pintype "input"))
      (node (ref "IC7") (pin "5") (pinfunction "+IN_5") (pintype "input"))
      (node (ref "IC8") (pin "1") (pinfunction "C_1") (pintype "passive"))
      (node (ref "IC9") (pin "10") (pinfunction "+IN_10") (pintype "input"))
      (node (ref "IC9") (pin "12") (pinfunction "+IN_12") (pintype "input"))
      (node (ref "IC9") (pin "3") (pinfunction "+IN_3") (pintype "input"))
      (node (ref "IC9") (pin "5") (pinfunction "+IN_5") (pintype "input"))
      (node (ref "J1") (pin "P1") (pinfunction "1_P1") (pintype "passive"))
      (node (ref "J2") (pin "P1") (pinfunction "1_P1") (pintype "passive"))
      (node (ref "J3") (pin "P1") (pinfunction "1_P1") (pintype "passive"))
      (node (ref "J4") (pin "P1") (pinfunction "1_P1") (pintype "passive"))
      (node (ref "J5") (pin "P1") (pinfunction "1_P1") (pintype "passive"))
      (node (ref "J6") (pin "P1") (pinfunction "1_P1") (pintype "passive"))
      (node (ref "JP1") (pin "3") (pinfunction "3_3") (pintype "passive"))
      (node (ref "JP1") (pin "4") (pinfunction "4_4") (pintype "passive"))
      (node (ref "JP1") (pin "5") (pinfunction "5_5") (pintype "passive"))
      (node (ref "JP1") (pin "6") (pinfunction "6_6") (pintype "passive"))
      (node (ref "JP1") (pin "7") (pinfunction "7_7") (pintype "passive"))
      (node (ref "JP1") (pin "8") (pinfunction "8_8") (pintype "passive"))
      (node (ref "JP2") (pin "3") (pinfunction "3_3") (pintype "passive"))
      (node (ref "JP2") (pin "5") (pinfunction "5_5") (pintype "passive"))
      (node (ref "JP2") (pin "9") (pinfunction "9_9") (pintype "passive"))
      (node (ref "JP3") (pin "1") (pinfunction "1_1") (pintype "passive"))
      (node (ref "Q1") (pin "E") (pinfunction "E_E") (pintype "passive"))
      (node (ref "Q2") (pin "E") (pinfunction "E_E") (pintype "passive"))
      (node (ref "Q3") (pin "E") (pinfunction "E_E") (pintype "passive"))
      (node (ref "Q4") (pin "E") (pinfunction "E_E") (pintype "passive"))
      (node (ref "Q6") (pin "E") (pinfunction "E_E") (pintype "passive"))
      (node (ref "R19") (pin "P$3") (pinfunction "A_P$3") (pintype "passive"))
      (node (ref "R20") (pin "P$3") (pinfunction "A_P$3") (pintype "passive"))
      (node (ref "R33") (pin "1") (pinfunction "1_1") (pintype "passive"))
      (node (ref "R36") (pin "P$3") (pinfunction "A_P$3") (pintype "passive"))
      (node (ref "R38") (pin "P$3") (pinfunction "A_P$3") (pintype "passive"))
      (node (ref "SW1") (pin "C") (pinfunction "C_C") (pintype "passive"))
      (node (ref "SW1") (pin "D") (pinfunction "1_D") (pintype "passive"))
      (node (ref "SW2") (pin "A") (pinfunction "P_A") (pintype "passive"))
      (node (ref "SW2") (pin "A'") (pinfunction "P1_A'") (pintype "passive"))
      (node (ref "UC1") (pin "20") (pinfunction "PB2/BOOT1_20") (pintype "bidirectional"))
      (node (ref "UC1") (pin "23") (pinfunction "VSS_1_23") (pintype "power_in"))
      (node (ref "UC1") (pin "35") (pinfunction "VSS_2_35") (pintype "power_in"))
      (node (ref "UC1") (pin "46") (pinfunction "PB9/TIM4_CH4_46") (pintype "input"))
      (node (ref "UC1") (pin "47") (pinfunction "VSS_3_47") (pintype "power_in"))
      (node (ref "UC1") (pin "8") (pinfunction "VSS_A_8") (pintype "power_in"))
    )
    (net (code "27") (name "JTCK") (class "Default")
      (node (ref "JP2") (pin "4") (pinfunction "4_4") (pintype "passive"))
      (node (ref "UC1") (pin "37") (pinfunction "PA14/JTCK/SWCLK_37") (pintype "bidirectional"))
    )
    (net (code "28") (name "JTDI") (class "Default")
      (node (ref "JP2") (pin "8") (pinfunction "8_8") (pintype "passive"))
      (node (ref "UC1") (pin "38") (pinfunction "PA15/JTDI_38") (pintype "bidirectional"))
    )
    (net (code "29") (name "JTDO") (class "Default")
      (node (ref "JP2") (pin "6") (pinfunction "6_6") (pintype "passive"))
      (node (ref "UC1") (pin "39") (pinfunction "PB3/JTDO_39") (pintype "bidirectional"))
    )
    (net (code "30") (name "JTMS") (class "Default")
      (node (ref "JP2") (pin "2") (pinfunction "2_2") (pintype "passive"))
      (node (ref "UC1") (pin "34") (pinfunction "PA13/JTMS/SWDIO_34") (pintype "bidirectional"))
    )
    (net (code "31") (name "Net-(C21-Pad1)") (class "Default")
      (node (ref "C21") (pin "1") (pinfunction "1_1") (pintype "passive"))
      (node (ref "R45") (pin "1") (pinfunction "1_1") (pintype "passive"))
      (node (ref "R46") (pin "2") (pinfunction "2_2") (pintype "passive"))
    )
    (net (code "32") (name "Net-(C24-Pad-)") (class "Default")
      (node (ref "C24") (pin "-") (pinfunction "-_-") (pintype "passive"))
      (node (ref "R50") (pin "2") (pinfunction "2_2") (pintype "passive"))
    )
    (net (code "33") (name "Net-(D1-PadA)") (class "Default")
      (node (ref "D1") (pin "A") (pinfunction "A_A") (pintype "passive"))
      (node (ref "JP1") (pin "1") (pinfunction "1_1") (pintype "passive"))
      (node (ref "JP1") (pin "2") (pinfunction "2_2") (pintype "passive"))
    )
    (net (code "34") (name "Net-(D2-PadC)") (class "Default")
      (node (ref "D2") (pin "C") (pinfunction "C_C") (pintype "passive"))
      (node (ref "JP1") (pin "10") (pinfunction "10_10") (pintype "passive"))
      (node (ref "JP1") (pin "9") (pinfunction "9_9") (pintype "passive"))
    )
    (net (code "35") (name "Net-(DISP1-A)") (class "Default")
      (node (ref "DISP1") (pin "12") (pinfunction "A_12") (pintype "passive"))
      (node (ref "DISP2") (pin "12") (pinfunction "A_12") (pintype "passive"))
      (node (ref "R9") (pin "2") (pinfunction "2_2") (pintype "passive"))
    )
    (net (code "36") (name "Net-(DISP1-B)") (class "Default")
      (node (ref "DISP1") (pin "10") (pinfunction "B_10") (pintype "passive"))
      (node (ref "DISP2") (pin "10") (pinfunction "B_10") (pintype "passive"))
      (node (ref "R10") (pin "2") (pinfunction "2_2") (pintype "passive"))
    )
    (net (code "37") (name "Net-(DISP1-C)") (class "Default")
      (node (ref "DISP1") (pin "9") (pinfunction "C_9") (pintype "passive"))
      (node (ref "DISP2") (pin "9") (pinfunction "C_9") (pintype "passive"))
      (node (ref "R12") (pin "2") (pinfunction "2_2") (pintype "passive"))
    )
    (net (code "38") (name "Net-(DISP1-D)") (class "Default")
      (node (ref "DISP1") (pin "7") (pinfunction "D_7") (pintype "passive"))
      (node (ref "DISP2") (pin "7") (pinfunction "D_7") (pintype "passive"))
      (node (ref "R18") (pin "2") (pinfunction "2_2") (pintype "passive"))
    )
    (net (code "39") (name "Net-(DISP1-E)") (class "Default")
      (node (ref "DISP1") (pin "1") (pinfunction "E_1") (pintype "passive"))
      (node (ref "DISP2") (pin "1") (pinfunction "E_1") (pintype "passive"))
      (node (ref "R13") (pin "2") (pinfunction "2_2") (pintype "passive"))
    )
    (net (code "40") (name "Net-(DISP1-F)") (class "Default")
      (node (ref "DISP1") (pin "18") (pinfunction "F_18") (pintype "passive"))
      (node (ref "DISP2") (pin "18") (pinfunction "F_18") (pintype "passive"))
      (node (ref "R4") (pin "2") (pinfunction "2_2") (pintype "passive"))
    )
    (net (code "41") (name "Net-(DISP1-G)") (class "Default")
      (node (ref "DISP1") (pin "17") (pinfunction "G_17") (pintype "passive"))
      (node (ref "DISP2") (pin "17") (pinfunction "G_17") (pintype "passive"))
      (node (ref "R5") (pin "2") (pinfunction "2_2") (pintype "passive"))
    )
    (net (code "42") (name "Net-(DISP1-H)") (class "Default")
      (node (ref "DISP1") (pin "15") (pinfunction "H_15") (pintype "passive"))
      (node (ref "DISP2") (pin "15") (pinfunction "H_15") (pintype "passive"))
      (node (ref "R6") (pin "2") (pinfunction "2_2") (pintype "passive"))
    )
    (net (code "43") (name "Net-(DISP1-J)") (class "Default")
      (node (ref "DISP1") (pin "14") (pinfunction "J_14") (pintype "passive"))
      (node (ref "DISP2") (pin "14") (pinfunction "J_14") (pintype "passive"))
      (node (ref "R7") (pin "2") (pinfunction "2_2") (pintype "passive"))
    )
    (net (code "44") (name "Net-(DISP1-K)") (class "Default")
      (node (ref "DISP1") (pin "6") (pinfunction "K_6") (pintype "passive"))
      (node (ref "DISP2") (pin "6") (pinfunction "K_6") (pintype "passive"))
      (node (ref "R17") (pin "2") (pinfunction "2_2") (pintype "passive"))
    )
    (net (code "45") (name "Net-(DISP1-K1)") (class "Default")
      (node (ref "DISP1") (pin "16") (pinfunction "K1_16") (pintype "passive"))
      (node (ref "Q1") (pin "C") (pinfunction "C_C") (pintype "passive"))
    )
    (net (code "46") (name "Net-(DISP1-K2)") (class "Default")
      (node (ref "DISP1") (pin "11") (pinfunction "K2_11") (pintype "passive"))
      (node (ref "Q2") (pin "C") (pinfunction "C_C") (pintype "passive"))
    )
    (net (code "47") (name "Net-(DISP1-L)") (class "Default")
      (node (ref "DISP1") (pin "5") (pinfunction "L_5") (pintype "passive"))
      (node (ref "DISP2") (pin "5") (pinfunction "L_5") (pintype "passive"))
      (node (ref "R16") (pin "2") (pinfunction "2_2") (pintype "passive"))
    )
    (net (code "48") (name "Net-(DISP1-M)") (class "Default")
      (node (ref "DISP1") (pin "4") (pinfunction "M_4") (pintype "passive"))
      (node (ref "DISP2") (pin "4") (pinfunction "M_4") (pintype "passive"))
      (node (ref "R15") (pin "2") (pinfunction "2_2") (pintype "passive"))
    )
    (net (code "49") (name "Net-(DISP1-N)") (class "Default")
      (node (ref "DISP1") (pin "2") (pinfunction "N_2") (pintype "passive"))
      (node (ref "DISP2") (pin "2") (pinfunction "N_2") (pintype "passive"))
      (node (ref "R14") (pin "2") (pinfunction "2_2") (pintype "passive"))
    )
    (net (code "50") (name "Net-(DISP1-P)") (class "Default")
      (node (ref "DISP1") (pin "13") (pinfunction "P_13") (pintype "passive"))
      (node (ref "DISP2") (pin "13") (pinfunction "P_13") (pintype "passive"))
      (node (ref "R8") (pin "2") (pinfunction "2_2") (pintype "passive"))
    )
    (net (code "51") (name "Net-(DISP2-K1)") (class "Default")
      (node (ref "DISP2") (pin "16") (pinfunction "K1_16") (pintype "passive"))
      (node (ref "Q3") (pin "C") (pinfunction "C_C") (pintype "passive"))
    )
    (net (code "52") (name "Net-(DISP2-K2)") (class "Default")
      (node (ref "DISP2") (pin "11") (pinfunction "K2_11") (pintype "passive"))
      (node (ref "Q4") (pin "C") (pinfunction "C_C") (pintype "passive"))
    )
    (net (code "53") (name "Net-(IC1A-QA)") (class "Default")
      (node (ref "IC1") (pin "15") (pinfunction "QA_15") (pintype "tri_state"))
      (node (ref "R7") (pin "1") (pinfunction "1_1") (pintype "passive"))
    )
    (net (code "54") (name "Net-(IC1A-QB)") (class "Default")
      (node (ref "IC1") (pin "1") (pinfunction "QB_1") (pintype "tri_state"))
      (node (ref "R17") (pin "1") (pinfunction "1_1") (pintype "passive"))
    )
    (net (code "55") (name "Net-(IC1A-QC)") (class "Default")
      (node (ref "IC1") (pin "2") (pinfunction "QC_2") (pintype "tri_state"))
      (node (ref "R16") (pin "1") (pinfunction "1_1") (pintype "passive"))
    )
    (net (code "56") (name "Net-(IC1A-QD)") (class "Default")
      (node (ref "IC1") (pin "3") (pinfunction "QD_3") (pintype "tri_state"))
      (node (ref "R15") (pin "1") (pinfunction "1_1") (pintype "passive"))
    )
    (net (code "57") (name "Net-(IC1A-QE)") (class "Default")
      (node (ref "IC1") (pin "4") (pinfunction "QE_4") (pintype "tri_state"))
      (node (ref "R14") (pin "1") (pinfunction "1_1") (pintype "passive"))
    )
    (net (code "58") (name "Net-(IC1A-QF)") (class "Default")
      (node (ref "IC1") (pin "5") (pinfunction "QF_5") (pintype "tri_state"))
      (node (ref "R8") (pin "1") (pinfunction "1_1") (pintype "passive"))
    )
    (net (code "59") (name "Net-(IC1A-SER)") (class "Default")
      (node (ref "IC1") (pin "14") (pinfunction "SER_14") (pintype "input"))
      (node (ref "IC2") (pin "9") (pinfunction "QH*_9") (pintype "tri_state"))
    )
    (net (code "60") (name "Net-(IC2A-QA)") (class "Default")
      (node (ref "IC2") (pin "15") (pinfunction "QA_15") (pintype "tri_state"))
      (node (ref "R9") (pin "1") (pinfunction "1_1") (pintype "passive"))
    )
    (net (code "61") (name "Net-(IC2A-QB)") (class "Default")
      (node (ref "IC2") (pin "1") (pinfunction "QB_1") (pintype "tri_state"))
      (node (ref "R10") (pin "1") (pinfunction "1_1") (pintype "passive"))
    )
    (net (code "62") (name "Net-(IC2A-QC)") (class "Default")
      (node (ref "IC2") (pin "2") (pinfunction "QC_2") (pintype "tri_state"))
      (node (ref "R12") (pin "1") (pinfunction "1_1") (pintype "passive"))
    )
    (net (code "63") (name "Net-(IC2A-QD)") (class "Default")
      (node (ref "IC2") (pin "3") (pinfunction "QD_3") (pintype "tri_state"))
      (node (ref "R18") (pin "1") (pinfunction "1_1") (pintype "passive"))
    )
    (net (code "64") (name "Net-(IC2A-QE)") (class "Default")
      (node (ref "IC2") (pin "4") (pinfunction "QE_4") (pintype "tri_state"))
      (node (ref "R13") (pin "1") (pinfunction "1_1") (pintype "passive"))
    )
    (net (code "65") (name "Net-(IC2A-QF)") (class "Default")
      (node (ref "IC2") (pin "5") (pinfunction "QF_5") (pintype "tri_state"))
      (node (ref "R4") (pin "1") (pinfunction "1_1") (pintype "passive"))
    )
    (net (code "66") (name "Net-(IC2A-QG)") (class "Default")
      (node (ref "IC2") (pin "6") (pinfunction "QG_6") (pintype "tri_state"))
      (node (ref "R5") (pin "1") (pinfunction "1_1") (pintype "passive"))
    )
    (net (code "67") (name "Net-(IC2A-QH)") (class "Default")
      (node (ref "IC2") (pin "7") (pinfunction "QH_7") (pintype "tri_state"))
      (node (ref "R6") (pin "1") (pinfunction "1_1") (pintype "passive"))
    )
    (net (code "68") (name "Net-(IC6-VIN)") (class "Default")
      (node (ref "C19") (pin "+") (pinfunction "+_+") (pintype "passive"))
      (node (ref "IC6") (pin "2") (pinfunction "VIN_2") (pintype "input"))
      (node (ref "R49") (pin "1") (pinfunction "1_1") (pintype "passive"))
    )
    (net (code "69") (name "Net-(IC7A--IN)") (class "Default")
      (node (ref "C16") (pin "1") (pinfunction "1_1") (pintype "passive"))
      (node (ref "IC7") (pin "2") (pinfunction "-IN_2") (pintype "input"))
      (node (ref "R34") (pin "1") (pinfunction "1_1") (pintype "passive"))
      (node (ref "R39") (pin "2") (pinfunction "2_2") (pintype "passive"))
      (node (ref "R41") (pin "2") (pinfunction "2_2") (pintype "passive"))
    )
    (net (code "70") (name "Net-(IC7B--IN)") (class "Default")
      (node (ref "C17") (pin "1") (pinfunction "1_1") (pintype "passive"))
      (node (ref "IC7") (pin "6") (pinfunction "-IN_6") (pintype "input"))
      (node (ref "R21") (pin "P$3") (pinfunction "A_P$3") (pintype "passive"))
      (node (ref "R35") (pin "1") (pinfunction "1_1") (pintype "passive"))
      (node (ref "R40") (pin "2") (pinfunction "2_2") (pintype "passive"))
      (node (ref "R42") (pin "2") (pinfunction "2_2") (pintype "passive"))
    )
    (net (code "71") (name "Net-(IC7C--IN)") (class "Default")
      (node (ref "C14") (pin "1") (pinfunction "1_1") (pintype "passive"))
      (node (ref "IC7") (pin "9") (pinfunction "-IN_9") (pintype "input"))
      (node (ref "R26") (pin "1") (pinfunction "1_1") (pintype "passive"))
      (node (ref "R31") (pin "2") (pinfunction "2_2") (pintype "passive"))
      (node (ref "R32") (pin "2") (pinfunction "2_2") (pintype "passive"))
    )
    (net (code "72") (name "Net-(IC7D--IN)") (class "Default")
      (node (ref "C13") (pin "1") (pinfunction "1_1") (pintype "passive"))
      (node (ref "IC7") (pin "13") (pinfunction "-IN_13") (pintype "input"))
      (node (ref "R25") (pin "1") (pinfunction "1_1") (pintype "passive"))
      (node (ref "R28") (pin "2") (pinfunction "2_2") (pintype "passive"))
      (node (ref "R30") (pin "2") (pinfunction "2_2") (pintype "passive"))
      (node (ref "R37") (pin "P$3") (pinfunction "A_P$3") (pintype "passive"))
    )
    (net (code "73") (name "Net-(IC9A--IN)") (class "Default")
      (node (ref "IC9") (pin "2") (pinfunction "-IN_2") (pintype "input"))
      (node (ref "R21") (pin "P$1") (pinfunction "E_P$1") (pintype "passive"))
      (node (ref "R52") (pin "1") (pinfunction "1_1") (pintype "passive"))
    )
    (net (code "74") (name "Net-(IC9A-OUT)") (class "Default")
      (node (ref "IC9") (pin "1") (pinfunction "OUT_1") (pintype "output"))
      (node (ref "R42") (pin "1") (pinfunction "1_1") (pintype "passive"))
      (node (ref "R52") (pin "2") (pinfunction "2_2") (pintype "passive"))
    )
    (net (code "75") (name "Net-(IC9B--IN)") (class "Default")
      (node (ref "IC9") (pin "6") (pinfunction "-IN_6") (pintype "input"))
      (node (ref "R53") (pin "1") (pinfunction "1_1") (pintype "passive"))
      (node (ref "R54") (pin "2") (pinfunction "2_2") (pintype "passive"))
    )
    (net (code "76") (name "Net-(IC9B-OUT)") (class "Default")
      (node (ref "IC9") (pin "7") (pinfunction "OUT_7") (pintype "output"))
      (node (ref "R41") (pin "1") (pinfunction "1_1") (pintype "passive"))
      (node (ref "R53") (pin "2") (pinfunction "2_2") (pintype "passive"))
    )
    (net (code "77") (name "Net-(IC9C--IN)") (class "Default")
      (node (ref "IC9") (pin "9") (pinfunction "-IN_9") (pintype "input"))
      (node (ref "R44") (pin "1") (pinfunction "1_1") (pintype "passive"))
      (node (ref "R47") (pin "2") (pinfunction "2_2") (pintype "passive"))
    )
    (net (code "78") (name "Net-(IC9C-OUT)") (class "Default")
      (node (ref "IC9") (pin "8") (pinfunction "OUT_8") (pintype "output"))
      (node (ref "R31") (pin "1") (pinfunction "1_1") (pintype "passive"))
      (node (ref "R44") (pin "2") (pinfunction "2_2") (pintype "passive"))
    )
    (net (code "79") (name "Net-(IC9D--IN)") (class "Default")
      (node (ref "IC9") (pin "13") (pinfunction "-IN_13") (pintype "input"))
      (node (ref "R37") (pin "P$1") (pinfunction "E_P$1") (pintype "passive"))
      (node (ref "R43") (pin "1") (pinfunction "1_1") (pintype "passive"))
    )
    (net (code "80") (name "Net-(IC9D-OUT)") (class "Default")
      (node (ref "IC9") (pin "14") (pinfunction "OUT_14") (pintype "output"))
      (node (ref "R30") (pin "1") (pinfunction "1_1") (pintype "passive"))
      (node (ref "R43") (pin "2") (pinfunction "2_2") (pintype "passive"))
    )
    (net (code "81") (name "Net-(IC10A--IN)") (class "Default")
      (node (ref "C29") (pin "1") (pinfunction "1_1") (pintype "passive"))
      (node (ref "IC10") (pin "2") (pinfunction "-IN_2") (pintype "input"))
      (node (ref "R50") (pin "1") (pinfunction "1_1") (pintype "passive"))
      (node (ref "R56") (pin "2") (pinfunction "2_2") (pintype "passive"))
    )
    (net (code "82") (name "Net-(IC10A-OUT)") (class "Default")
      (node (ref "C29") (pin "2") (pinfunction "2_2") (pintype "passive"))
      (node (ref "IC10") (pin "1") (pinfunction "OUT_1") (pintype "output"))
      (node (ref "R55") (pin "2") (pinfunction "2_2") (pintype "passive"))
    )
    (net (code "83") (name "Net-(IC10B-+IN)") (class "Default")
      (node (ref "C22") (pin "1") (pinfunction "1_1") (pintype "passive"))
      (node (ref "IC10") (pin "5") (pinfunction "+IN_5") (pintype "input"))
      (node (ref "R46") (pin "1") (pinfunction "1_1") (pintype "passive"))
    )
    (net (code "84") (name "Net-(IC10B--IN)") (class "Default")
      (node (ref "C21") (pin "2") (pinfunction "2_2") (pintype "passive"))
      (node (ref "C24") (pin "+") (pinfunction "+_+") (pintype "passive"))
      (node (ref "IC10") (pin "6") (pinfunction "-IN_6") (pintype "input"))
      (node (ref "IC10") (pin "7") (pinfunction "OUT_7") (pintype "output"))
    )
    (net (code "85") (name "Net-(J1-3)") (class "Default")
      (node (ref "J1") (pin "P3") (pinfunction "3_P3") (pintype "passive"))
      (node (ref "R29") (pin "1") (pinfunction "1_1") (pintype "passive"))
    )
    (net (code "86") (name "Net-(J2-3)") (class "Default")
      (node (ref "J2") (pin "P3") (pinfunction "3_P3") (pintype "passive"))
      (node (ref "R54") (pin "1") (pinfunction "1_1") (pintype "passive"))
    )
    (net (code "87") (name "Net-(J3-3)") (class "Default")
      (node (ref "J3") (pin "P3") (pinfunction "3_P3") (pintype "passive"))
      (node (ref "R24") (pin "1") (pinfunction "1_1") (pintype "passive"))
    )
    (net (code "88") (name "Net-(J4-3)") (class "Default")
      (node (ref "J4") (pin "P3") (pinfunction "3_P3") (pintype "passive"))
      (node (ref "R48") (pin "1") (pinfunction "1_1") (pintype "passive"))
    )
    (net (code "89") (name "Net-(J5-3)") (class "Default")
      (node (ref "J5") (pin "P3") (pinfunction "3_P3") (pintype "passive"))
      (node (ref "R47") (pin "1") (pinfunction "1_1") (pintype "passive"))
    )
    (net (code "90") (name "Net-(J6-3)") (class "Default")
      (node (ref "J6") (pin "P3") (pinfunction "3_P3") (pintype "passive"))
      (node (ref "R55") (pin "1") (pinfunction "1_1") (pintype "passive"))
      (node (ref "R56") (pin "1") (pinfunction "1_1") (pintype "passive"))
    )
    (net (code "91") (name "Net-(Q1-PadB)") (class "Default")
      (node (ref "Q1") (pin "B") (pinfunction "B_B") (pintype "passive"))
      (node (ref "R1") (pin "2") (pinfunction "2_2") (pintype "passive"))
    )
    (net (code "92") (name "Net-(Q2-PadB)") (class "Default")
      (node (ref "Q2") (pin "B") (pinfunction "B_B") (pintype "passive"))
      (node (ref "R2") (pin "2") (pinfunction "2_2") (pintype "passive"))
    )
    (net (code "93") (name "Net-(Q3-PadB)") (class "Default")
      (node (ref "Q3") (pin "B") (pinfunction "B_B") (pintype "passive"))
      (node (ref "R3") (pin "2") (pinfunction "2_2") (pintype "passive"))
    )
    (net (code "94") (name "Net-(Q4-PadB)") (class "Default")
      (node (ref "Q4") (pin "B") (pinfunction "B_B") (pintype "passive"))
      (node (ref "R11") (pin "2") (pinfunction "2_2") (pintype "passive"))
    )
    (net (code "95") (name "Net-(Q6-PadB)") (class "Default")
      (node (ref "Q6") (pin "B") (pinfunction "B_B") (pintype "passive"))
      (node (ref "R29") (pin "2") (pinfunction "2_2") (pintype "passive"))
    )
    (net (code "96") (name "Net-(R20-S)") (class "Default")
      (node (ref "R20") (pin "P$2") (pinfunction "S_P$2") (pintype "passive"))
      (node (ref "R39") (pin "1") (pinfunction "1_1") (pintype "passive"))
    )
    (net (code "97") (name "Net-(R21-S)") (class "Default")
      (node (ref "R21") (pin "P$2") (pinfunction "S_P$2") (pintype "passive"))
      (node (ref "R24") (pin "2") (pinfunction "2_2") (pintype "passive"))
    )
    (net (code "98") (name "Net-(R36-S)") (class "Default")
      (node (ref "R28") (pin "1") (pinfunction "1_1") (pintype "passive"))
      (node (ref "R36") (pin "P$2") (pinfunction "S_P$2") (pintype "passive"))
    )
    (net (code "99") (name "Net-(R37-S)") (class "Default")
      (node (ref "R37") (pin "P$2") (pinfunction "S_P$2") (pintype "passive"))
      (node (ref "R48") (pin "2") (pinfunction "2_2") (pintype "passive"))
    )
    (net (code "100") (name "Net-(R38-S)") (class "Default")
      (node (ref "R32") (pin "1") (pinfunction "1_1") (pintype "passive"))
      (node (ref "R38") (pin "P$2") (pinfunction "S_P$2") (pintype "passive"))
    )
    (net (code "101") (name "Net-(UC1-PD0-OSC_IN)") (class "Default")
      (node (ref "C9") (pin "2") (pinfunction "2_2") (pintype "passive"))
      (node (ref "Q5") (pin "2") (pinfunction "2_2") (pintype "passive"))
      (node (ref "UC1") (pin "5") (pinfunction "PD0-OSC_IN_5") (pintype "input"))
    )
    (net (code "102") (name "Net-(UC1-PD1-OSC_OUT)") (class "Default")
      (node (ref "C10") (pin "2") (pinfunction "2_2") (pintype "passive"))
      (node (ref "Q5") (pin "1") (pinfunction "1_1") (pintype "passive"))
      (node (ref "UC1") (pin "6") (pinfunction "PD1-OSC_OUT_6") (pintype "input"))
    )
    (net (code "103") (name "PARAM1_CV") (class "Default")
      (node (ref "C13") (pin "2") (pinfunction "2_2") (pintype "passive"))
      (node (ref "IC4") (pin "1") (pinfunction "CH0_1") (pintype "bidirectional"))
      (node (ref "IC7") (pin "14") (pinfunction "OUT_14") (pintype "output"))
      (node (ref "R25") (pin "2") (pinfunction "2_2") (pintype "passive"))
    )
    (net (code "104") (name "PARAM2_CV") (class "Default")
      (node (ref "C14") (pin "2") (pinfunction "2_2") (pintype "passive"))
      (node (ref "IC4") (pin "2") (pinfunction "CH1_2") (pintype "bidirectional"))
      (node (ref "IC7") (pin "8") (pinfunction "OUT_8") (pintype "output"))
      (node (ref "R26") (pin "2") (pinfunction "2_2") (pintype "passive"))
    )
    (net (code "105") (name "PITCH_CV") (class "Default")
      (node (ref "C16") (pin "2") (pinfunction "2_2") (pintype "passive"))
      (node (ref "IC4") (pin "3") (pinfunction "CH2_3") (pintype "bidirectional"))
      (node (ref "IC7") (pin "1") (pinfunction "OUT_1") (pintype "output"))
      (node (ref "R34") (pin "2") (pinfunction "2_2") (pintype "passive"))
    )
    (net (code "106") (name "RESET") (class "Default")
      (node (ref "JP2") (pin "10") (pinfunction "10_10") (pintype "passive"))
      (node (ref "R22") (pin "1") (pinfunction "1_1") (pintype "passive"))
      (node (ref "SW2") (pin "B") (pinfunction "S_B") (pintype "passive"))
      (node (ref "SW2") (pin "B'") (pinfunction "S1_B'") (pintype "passive"))
      (node (ref "UC1") (pin "7") (pinfunction "NRST_7") (pintype "input"))
    )
    (net (code "107") (name "RX") (class "Default")
      (node (ref "JP3") (pin "4") (pinfunction "4_4") (pintype "passive"))
      (node (ref "UC1") (pin "31") (pinfunction "PA10/USART1_RX/TIM1_CH3_31") (pintype "bidirectional"))
    )
    (net (code "108") (name "TX") (class "Default")
      (node (ref "JP3") (pin "5") (pinfunction "5_5") (pintype "passive"))
      (node (ref "UC1") (pin "30") (pinfunction "PA9/USART1_TX/TIM1_CH2_30") (pintype "input"))
    )
    (net (code "109") (name "VCC") (class "Default")
      (node (ref "C23") (pin "1") (pinfunction "1_1") (pintype "passive"))
      (node (ref "C25") (pin "+") (pinfunction "+_+") (pintype "passive"))
      (node (ref "C28") (pin "1") (pinfunction "1_1") (pintype "passive"))
      (node (ref "D1") (pin "C") (pinfunction "C_C") (pintype "passive"))
      (node (ref "IC10") (pin "8") (pinfunction "V+_8") (pintype "power_in"))
      (node (ref "IC9") (pin "4") (pinfunction "V+_4") (pintype "power_in"))
      (node (ref "R49") (pin "2") (pinfunction "2_2") (pintype "passive"))
    )
    (net (code "110") (name "VEE") (class "Default")
      (node (ref "C20") (pin "2") (pinfunction "2_2") (pintype "passive"))
      (node (ref "C27") (pin "2") (pinfunction "2_2") (pintype "passive"))
      (node (ref "C30") (pin "-") (pinfunction "-_-") (pintype "passive"))
      (node (ref "D2") (pin "A") (pinfunction "A_A") (pintype "passive"))
      (node (ref "IC10") (pin "4") (pinfunction "V-_4") (pintype "power_in"))
      (node (ref "IC9") (pin "11") (pinfunction "V-_11") (pintype "power_in"))
      (node (ref "R51") (pin "1") (pinfunction "1_1") (pintype "passive"))
    )
    (net (code "111") (name "unconnected-(DISP1-DP-Pad8)") (class "Default")
      (node (ref "DISP1") (pin "8") (pinfunction "DP_8") (pintype "passive"))
    )
    (net (code "112") (name "unconnected-(DISP2-DP-Pad8)") (class "Default")
      (node (ref "DISP2") (pin "8") (pinfunction "DP_8") (pintype "passive"))
    )
    (net (code "113") (name "unconnected-(IC1A-QG-Pad6)") (class "Default")
      (node (ref "IC1") (pin "6") (pinfunction "QG_6") (pintype "tri_state"))
    )
    (net (code "114") (name "unconnected-(IC1A-QH*-Pad9)") (class "Default")
      (node (ref "IC1") (pin "9") (pinfunction "QH*_9") (pintype "tri_state"))
    )
    (net (code "115") (name "unconnected-(IC1A-QH-Pad7)") (class "Default")
      (node (ref "IC1") (pin "7") (pinfunction "QH_7") (pintype "tri_state"))
    )
    (net (code "116") (name "unconnected-(J1-2-PadP2)") (class "Default")
      (node (ref "J1") (pin "P2") (pinfunction "2_P2") (pintype "passive"))
    )
    (net (code "117") (name "unconnected-(J2-2-PadP2)") (class "Default")
      (node (ref "J2") (pin "P2") (pinfunction "2_P2") (pintype "passive"))
    )
    (net (code "118") (name "unconnected-(J3-2-PadP2)") (class "Default")
      (node (ref "J3") (pin "P2") (pinfunction "2_P2") (pintype "passive"))
    )
    (net (code "119") (name "unconnected-(J4-2-PadP2)") (class "Default")
      (node (ref "J4") (pin "P2") (pinfunction "2_P2") (pintype "passive"))
    )
    (net (code "120") (name "unconnected-(J5-2-PadP2)") (class "Default")
      (node (ref "J5") (pin "P2") (pinfunction "2_P2") (pintype "passive"))
    )
    (net (code "121") (name "unconnected-(J6-2-PadP2)") (class "Default")
      (node (ref "J6") (pin "P2") (pinfunction "2_P2") (pintype "passive"))
    )
    (net (code "122") (name "unconnected-(JP2-Pad7)") (class "Default")
      (node (ref "JP2") (pin "7") (pinfunction "7_7") (pintype "passive"))
    )
    (net (code "123") (name "unconnected-(JP3-Pad2)") (class "Default")
      (node (ref "JP3") (pin "2") (pinfunction "2_2") (pintype "passive"))
    )
    (net (code "124") (name "unconnected-(JP3-Pad3)") (class "Default")
      (node (ref "JP3") (pin "3") (pinfunction "3_3") (pintype "passive"))
    )
    (net (code "125") (name "unconnected-(JP3-Pad6)") (class "Default")
      (node (ref "JP3") (pin "6") (pinfunction "6_6") (pintype "passive"))
    )
    (net (code "126") (name "unconnected-(UC1-PA0_WKUP{slash}USART2_CTS{slash}ADC12_IN0{slash}TIM2_CH1_ETR-Pad10)") (class "Default")
      (node (ref "UC1") (pin "10") (pinfunction "PA0_WKUP/USART2_CTS/ADC12_IN0/TIM2_CH1_ETR_10") (pintype "bidirectional"))
    )
    (net (code "127") (name "unconnected-(UC1-PA1{slash}USART2_RTS{slash}ADC12_IN1{slash}TIM2_CH2-Pad11)") (class "Default")
      (node (ref "UC1") (pin "11") (pinfunction "PA1/USART2_RTS/ADC12_IN1/TIM2_CH2_11") (pintype "bidirectional"))
    )
    (net (code "128") (name "unconnected-(UC1-PA2{slash}USART2_TX{slash}ADC12_IN2{slash}TIM2_CH3-Pad12)") (class "Default")
      (node (ref "UC1") (pin "12") (pinfunction "PA2/USART2_TX/ADC12_IN2/TIM2_CH3_12") (pintype "bidirectional"))
    )
    (net (code "129") (name "unconnected-(UC1-PA8{slash}USART1_CK{slash}TIM1_CH1{slash}MCO-Pad29)") (class "Default")
      (node (ref "UC1") (pin "29") (pinfunction "PA8/USART1_CK/TIM1_CH1/MCO_29") (pintype "bidirectional"))
    )
    (net (code "130") (name "unconnected-(UC1-PA11{slash}USART1_CTS{slash}CAN_RX{slash}TIM1_CH4{slash}USBDM-Pad32)") (class "Default")
      (node (ref "UC1") (pin "32") (pinfunction "PA11/USART1_CTS/CAN_RX/TIM1_CH4/USBDM_32") (pintype "bidirectional"))
    )
    (net (code "131") (name "unconnected-(UC1-PA12{slash}USART1_RTS{slash}CAN_TX{slash}TIM1_ETR{slash}USBDP-Pad33)") (class "Default")
      (node (ref "UC1") (pin "33") (pinfunction "PA12/USART1_RTS/CAN_TX/TIM1_ETR/USBDP_33") (pintype "bidirectional"))
    )
    (net (code "132") (name "unconnected-(UC1-PB4{slash}NJTRST-Pad40)") (class "Default")
      (node (ref "UC1") (pin "40") (pinfunction "PB4/NJTRST_40") (pintype "bidirectional"))
    )
    (net (code "133") (name "unconnected-(UC1-PB14{slash}SPI2_MISO{slash}USART3_RTS{slash}TIM1_CH2N-Pad27)") (class "Default")
      (node (ref "UC1") (pin "27") (pinfunction "PB14/SPI2_MISO/USART3_RTS/TIM1_CH2N_27") (pintype "input"))
    )
  )
)
